# M111C.net
KiCad netlist of a schematic drawn in EAGLE
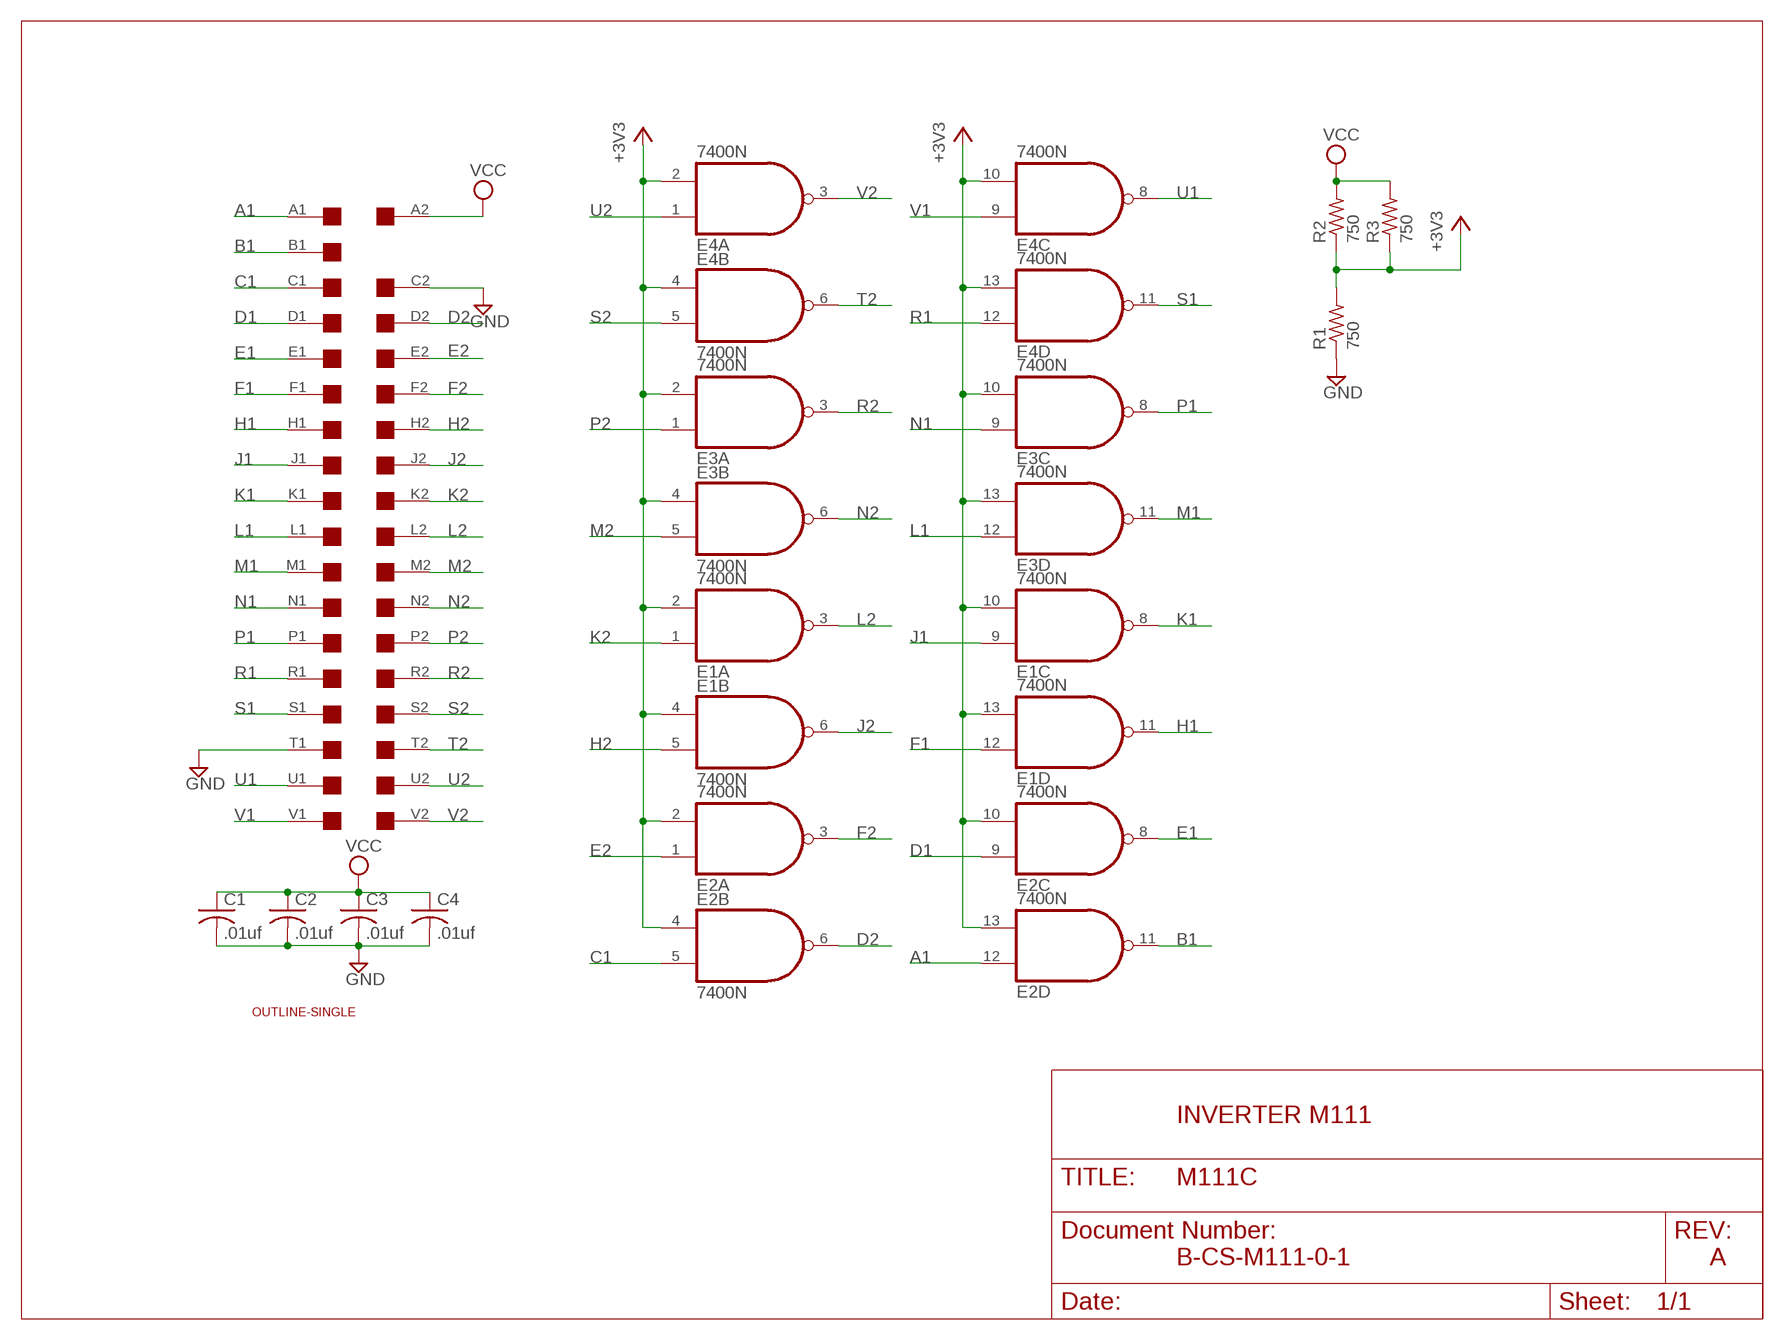
[diagram p0: schematic, sheet 1]

(export (version "E")
  (design (tool "Eeschema 10.0.6"))
  (components
    (comp (ref "A")
      (value "EDGE-2CONNECTOR")
      (footprint "eagle-import:EDGE-CON2")
      (libsource (lib "eagle-import") (part "EDGE-2CONNECTOR"))
    )
    (comp (ref "C1")
      (value ".01uf")
      (footprint "eagle-import:C050-025X075")
      (libsource (lib "eagle-import") (part "C-US050-025X075"))
    )
    (comp (ref "C2")
      (value ".01uf")
      (footprint "eagle-import:C050-025X075")
      (libsource (lib "eagle-import") (part "C-US050-025X075"))
    )
    (comp (ref "C3")
      (value ".01uf")
      (footprint "eagle-import:C050-025X075")
      (libsource (lib "eagle-import") (part "C-US050-025X075"))
    )
    (comp (ref "C4")
      (value ".01uf")
      (footprint "eagle-import:C050-025X075")
      (libsource (lib "eagle-import") (part "C-US050-025X075"))
    )
    (comp (ref "E1")
      (value "7400N")
      (footprint "eagle-import:DIL14")
      (libsource (lib "eagle-import") (part "7400N"))
    )
    (comp (ref "E2")
      (value "7400N")
      (footprint "eagle-import:DIL14")
      (libsource (lib "eagle-import") (part "7400N"))
    )
    (comp (ref "E3")
      (value "7400N")
      (footprint "eagle-import:DIL14")
      (libsource (lib "eagle-import") (part "7400N"))
    )
    (comp (ref "E4")
      (value "7400N")
      (footprint "eagle-import:DIL14")
      (libsource (lib "eagle-import") (part "7400N"))
    )
    (comp (ref "R1")
      (value "750")
      (footprint "eagle-import:0207_10")
      (libsource (lib "eagle-import") (part "R-US_0207/10"))
    )
    (comp (ref "R2")
      (value "750")
      (footprint "eagle-import:0207_10")
      (libsource (lib "eagle-import") (part "R-US_0207/10"))
    )
    (comp (ref "R3")
      (value "750")
      (footprint "eagle-import:0207_10")
      (libsource (lib "eagle-import") (part "R-US_0207/10"))
    )
    (comp (ref "U$1")
      (value "OUTLINE-SINGLE")
      (footprint "eagle-import:SINGLE")
      (libsource (lib "eagle-import") (part "OUTLINE-SINGLE"))
    )
  )
  (nets
    (net (code "1") (name "+3V3") (class "Default")
      (node (ref "E1") (pin "10") (pinfunction "I1_10") (pintype "input"))
      (node (ref "E1") (pin "13") (pinfunction "I1_13") (pintype "input"))
      (node (ref "E1") (pin "2") (pinfunction "I1_2") (pintype "input"))
      (node (ref "E1") (pin "4") (pinfunction "I0_4") (pintype "input"))
      (node (ref "E2") (pin "10") (pinfunction "I1_10") (pintype "input"))
      (node (ref "E2") (pin "13") (pinfunction "I1_13") (pintype "input"))
      (node (ref "E2") (pin "2") (pinfunction "I1_2") (pintype "input"))
      (node (ref "E2") (pin "4") (pinfunction "I0_4") (pintype "input"))
      (node (ref "E3") (pin "10") (pinfunction "I1_10") (pintype "input"))
      (node (ref "E3") (pin "13") (pinfunction "I1_13") (pintype "input"))
      (node (ref "E3") (pin "2") (pinfunction "I1_2") (pintype "input"))
      (node (ref "E3") (pin "4") (pinfunction "I0_4") (pintype "input"))
      (node (ref "E4") (pin "10") (pinfunction "I1_10") (pintype "input"))
      (node (ref "E4") (pin "13") (pinfunction "I1_13") (pintype "input"))
      (node (ref "E4") (pin "2") (pinfunction "I1_2") (pintype "input"))
      (node (ref "E4") (pin "4") (pinfunction "I0_4") (pintype "input"))
      (node (ref "R1") (pin "2") (pinfunction "2_2") (pintype "passive"))
      (node (ref "R2") (pin "1") (pinfunction "1_1") (pintype "passive"))
      (node (ref "R3") (pin "1") (pinfunction "1_1") (pintype "passive"))
    )
    (net (code "2") (name "/A1") (class "Default")
      (node (ref "A") (pin "A1") (pinfunction "1_A1") (pintype "bidirectional"))
      (node (ref "E2") (pin "12") (pinfunction "I0_12") (pintype "input"))
    )
    (net (code "3") (name "/B1") (class "Default")
      (node (ref "A") (pin "B1") (pinfunction "1_B1") (pintype "bidirectional"))
      (node (ref "E2") (pin "11") (pinfunction "O_11") (pintype "output"))
    )
    (net (code "4") (name "/C1") (class "Default")
      (node (ref "A") (pin "C1") (pinfunction "1_C1") (pintype "bidirectional"))
      (node (ref "E2") (pin "5") (pinfunction "I1_5") (pintype "input"))
    )
    (net (code "5") (name "/D1") (class "Default")
      (node (ref "A") (pin "D1") (pinfunction "1_D1") (pintype "bidirectional"))
      (node (ref "E2") (pin "9") (pinfunction "I0_9") (pintype "input"))
    )
    (net (code "6") (name "/D2") (class "Default")
      (node (ref "A") (pin "D2") (pinfunction "1_D2") (pintype "bidirectional"))
      (node (ref "E2") (pin "6") (pinfunction "O_6") (pintype "output"))
    )
    (net (code "7") (name "/E1") (class "Default")
      (node (ref "A") (pin "E1") (pinfunction "1_E1") (pintype "bidirectional"))
      (node (ref "E2") (pin "8") (pinfunction "O_8") (pintype "output"))
    )
    (net (code "8") (name "/E2") (class "Default")
      (node (ref "A") (pin "E2") (pinfunction "1_E2") (pintype "bidirectional"))
      (node (ref "E2") (pin "1") (pinfunction "I0_1") (pintype "input"))
    )
    (net (code "9") (name "/F1") (class "Default")
      (node (ref "A") (pin "F1") (pinfunction "1_F1") (pintype "bidirectional"))
      (node (ref "E1") (pin "12") (pinfunction "I0_12") (pintype "input"))
    )
    (net (code "10") (name "/F2") (class "Default")
      (node (ref "A") (pin "F2") (pinfunction "1_F2") (pintype "bidirectional"))
      (node (ref "E2") (pin "3") (pinfunction "O_3") (pintype "output"))
    )
    (net (code "11") (name "/H1") (class "Default")
      (node (ref "A") (pin "H1") (pinfunction "1_H1") (pintype "bidirectional"))
      (node (ref "E1") (pin "11") (pinfunction "O_11") (pintype "output"))
    )
    (net (code "12") (name "/H2") (class "Default")
      (node (ref "A") (pin "H2") (pinfunction "1_H2") (pintype "bidirectional"))
      (node (ref "E1") (pin "5") (pinfunction "I1_5") (pintype "input"))
    )
    (net (code "13") (name "/J1") (class "Default")
      (node (ref "A") (pin "J1") (pinfunction "1_J1") (pintype "bidirectional"))
      (node (ref "E1") (pin "9") (pinfunction "I0_9") (pintype "input"))
    )
    (net (code "14") (name "/J2") (class "Default")
      (node (ref "A") (pin "J2") (pinfunction "1_J2") (pintype "bidirectional"))
      (node (ref "E1") (pin "6") (pinfunction "O_6") (pintype "output"))
    )
    (net (code "15") (name "/K1") (class "Default")
      (node (ref "A") (pin "K1") (pinfunction "1_K1") (pintype "bidirectional"))
      (node (ref "E1") (pin "8") (pinfunction "O_8") (pintype "output"))
    )
    (net (code "16") (name "/K2") (class "Default")
      (node (ref "A") (pin "K2") (pinfunction "1_K2") (pintype "bidirectional"))
      (node (ref "E1") (pin "1") (pinfunction "I0_1") (pintype "input"))
    )
    (net (code "17") (name "/L1") (class "Default")
      (node (ref "A") (pin "L1") (pinfunction "1_L1") (pintype "bidirectional"))
      (node (ref "E3") (pin "12") (pinfunction "I0_12") (pintype "input"))
    )
    (net (code "18") (name "/L2") (class "Default")
      (node (ref "A") (pin "L2") (pinfunction "1_L2") (pintype "bidirectional"))
      (node (ref "E1") (pin "3") (pinfunction "O_3") (pintype "output"))
    )
    (net (code "19") (name "/M1") (class "Default")
      (node (ref "A") (pin "M1") (pinfunction "1_M1") (pintype "bidirectional"))
      (node (ref "E3") (pin "11") (pinfunction "O_11") (pintype "output"))
    )
    (net (code "20") (name "/M2") (class "Default")
      (node (ref "A") (pin "M2") (pinfunction "1_M2") (pintype "bidirectional"))
      (node (ref "E3") (pin "5") (pinfunction "I1_5") (pintype "input"))
    )
    (net (code "21") (name "/N1") (class "Default")
      (node (ref "A") (pin "N1") (pinfunction "1_N1") (pintype "bidirectional"))
      (node (ref "E3") (pin "9") (pinfunction "I0_9") (pintype "input"))
    )
    (net (code "22") (name "/N2") (class "Default")
      (node (ref "A") (pin "N2") (pinfunction "1_N2") (pintype "bidirectional"))
      (node (ref "E3") (pin "6") (pinfunction "O_6") (pintype "output"))
    )
    (net (code "23") (name "/P1") (class "Default")
      (node (ref "A") (pin "P1") (pinfunction "1_P1") (pintype "bidirectional"))
      (node (ref "E3") (pin "8") (pinfunction "O_8") (pintype "output"))
    )
    (net (code "24") (name "/P2") (class "Default")
      (node (ref "A") (pin "P2") (pinfunction "1_P2") (pintype "bidirectional"))
      (node (ref "E3") (pin "1") (pinfunction "I0_1") (pintype "input"))
    )
    (net (code "25") (name "/R1") (class "Default")
      (node (ref "A") (pin "R1") (pinfunction "1_R1") (pintype "bidirectional"))
      (node (ref "E4") (pin "12") (pinfunction "I0_12") (pintype "input"))
    )
    (net (code "26") (name "/R2") (class "Default")
      (node (ref "A") (pin "R2") (pinfunction "1_R2") (pintype "bidirectional"))
      (node (ref "E3") (pin "3") (pinfunction "O_3") (pintype "output"))
    )
    (net (code "27") (name "/S1") (class "Default")
      (node (ref "A") (pin "S1") (pinfunction "1_S1") (pintype "bidirectional"))
      (node (ref "E4") (pin "11") (pinfunction "O_11") (pintype "output"))
    )
    (net (code "28") (name "/S2") (class "Default")
      (node (ref "A") (pin "S2") (pinfunction "1_S2") (pintype "bidirectional"))
      (node (ref "E4") (pin "5") (pinfunction "I1_5") (pintype "input"))
    )
    (net (code "29") (name "/T2") (class "Default")
      (node (ref "A") (pin "T2") (pinfunction "1_T2") (pintype "bidirectional"))
      (node (ref "E4") (pin "6") (pinfunction "O_6") (pintype "output"))
    )
    (net (code "30") (name "/U1") (class "Default")
      (node (ref "A") (pin "U1") (pinfunction "1_U1") (pintype "bidirectional"))
      (node (ref "E4") (pin "8") (pinfunction "O_8") (pintype "output"))
    )
    (net (code "31") (name "/U2") (class "Default")
      (node (ref "A") (pin "U2") (pinfunction "1_U2") (pintype "bidirectional"))
      (node (ref "E4") (pin "1") (pinfunction "I0_1") (pintype "input"))
    )
    (net (code "32") (name "/V1") (class "Default")
      (node (ref "A") (pin "V1") (pinfunction "1_V1") (pintype "bidirectional"))
      (node (ref "E4") (pin "9") (pinfunction "I0_9") (pintype "input"))
    )
    (net (code "33") (name "/V2") (class "Default")
      (node (ref "A") (pin "V2") (pinfunction "1_V2") (pintype "bidirectional"))
      (node (ref "E4") (pin "3") (pinfunction "O_3") (pintype "output"))
    )
    (net (code "34") (name "GND") (class "Default")
      (node (ref "A") (pin "C2") (pinfunction "1_C2") (pintype "bidirectional"))
      (node (ref "A") (pin "T1") (pinfunction "1_T1") (pintype "bidirectional"))
      (node (ref "C1") (pin "2") (pinfunction "2_2") (pintype "passive"))
      (node (ref "C2") (pin "2") (pinfunction "2_2") (pintype "passive"))
      (node (ref "C3") (pin "2") (pinfunction "2_2") (pintype "passive"))
      (node (ref "C4") (pin "2") (pinfunction "2_2") (pintype "passive"))
      (node (ref "R1") (pin "1") (pinfunction "1_1") (pintype "passive"))
    )
    (net (code "35") (name "VCC") (class "Default")
      (node (ref "A") (pin "A2") (pinfunction "1_A2") (pintype "bidirectional"))
      (node (ref "C1") (pin "1") (pinfunction "1_1") (pintype "passive"))
      (node (ref "C2") (pin "1") (pinfunction "1_1") (pintype "passive"))
      (node (ref "C3") (pin "1") (pinfunction "1_1") (pintype "passive"))
      (node (ref "C4") (pin "1") (pinfunction "1_1") (pintype "passive"))
      (node (ref "R2") (pin "2") (pinfunction "2_2") (pintype "passive"))
      (node (ref "R3") (pin "2") (pinfunction "2_2") (pintype "passive"))
    )
  )
)
